# Bridge.net
KiCad netlist of a schematic drawn in Altium Designer
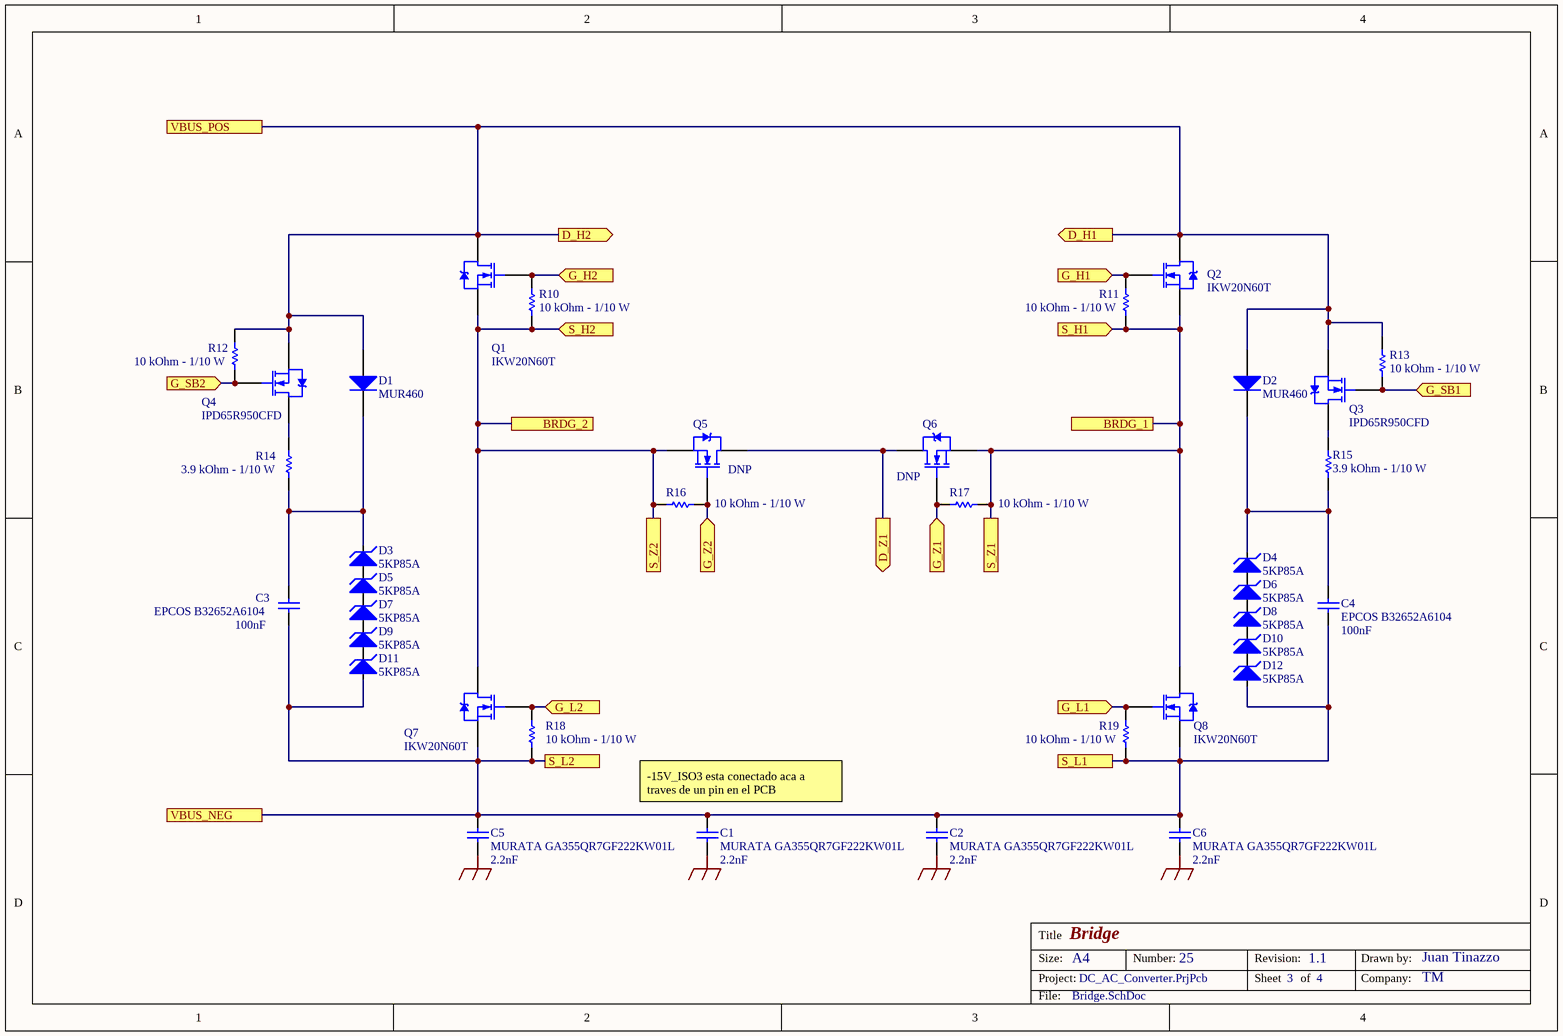
[diagram p0: Bridge.SchDoc]

(export (version "E")
  (design (tool "Eeschema 10.0.6"))
  (components
    (comp (ref "C1")
      (value "MURATA GA355QR7GF222KW01L")
      (footprint "Chip2PinSM127P600-8N_safety")
      (description "Safety Standard Certified Ceramic Y2 2.2nF 250Vac")
      (fields (field (name "ALTIUM_VALUE") "2.2nF") (field (name "PUBLISHER") "Altium Limited"))
      (libsource (lib "Capacitor") (part "MURATA GA355QR7GF222KW01L"))
    )
    (comp (ref "C2")
      (value "MURATA GA355QR7GF222KW01L")
      (footprint "Chip2PinSM127P600-8N_safety")
      (description "Safety Standard Certified Ceramic Y2 2.2nF 250Vac")
      (fields (field (name "ALTIUM_VALUE") "2.2nF") (field (name "PUBLISHER") "Altium Limited"))
      (libsource (lib "Capacitor") (part "MURATA GA355QR7GF222KW01L"))
    )
    (comp (ref "C3")
      (value "EPCOS B32652A6104")
      (footprint "MKP  pitch:15mm size:7mm x 18mm")
      (description "MKP High pulse (wound) 100nF 630Vdc")
      (fields (field (name "ALTIUM_VALUE") "100nF") (field (name "PUBLISHER") "Altium Limited"))
      (libsource (lib "Capacitor") (part "EPCOS B32652A6104"))
    )
    (comp (ref "C4")
      (value "EPCOS B32652A6104")
      (footprint "MKP  pitch:15mm size:7mm x 18mm")
      (description "MKP High pulse (wound) 100nF 630Vdc")
      (fields (field (name "ALTIUM_VALUE") "100nF") (field (name "PUBLISHER") "Altium Limited"))
      (libsource (lib "Capacitor") (part "EPCOS B32652A6104"))
    )
    (comp (ref "C5")
      (value "MURATA GA355QR7GF222KW01L")
      (footprint "Chip2PinSM127P600-8N_safety")
      (description "Safety Standard Certified Ceramic Y2 2.2nF 250Vac")
      (fields (field (name "ALTIUM_VALUE") "2.2nF") (field (name "PUBLISHER") "Altium Limited"))
      (libsource (lib "Capacitor") (part "MURATA GA355QR7GF222KW01L"))
    )
    (comp (ref "C6")
      (value "MURATA GA355QR7GF222KW01L")
      (footprint "Chip2PinSM127P600-8N_safety")
      (description "Safety Standard Certified Ceramic Y2 2.2nF 250Vac")
      (fields (field (name "ALTIUM_VALUE") "2.2nF") (field (name "PUBLISHER") "Altium Limited"))
      (libsource (lib "Capacitor") (part "MURATA GA355QR7GF222KW01L"))
    )
    (comp (ref "D1")
      (value "MUR460")
      (footprint "SMC")
      (description "Default Diode")
      (fields (field (name "PUBLISHER") "Altium Limited"))
      (libsource (lib "Miscellaneous Devices") (part "Diode"))
    )
    (comp (ref "D2")
      (value "MUR460")
      (footprint "SMC")
      (description "Default Diode")
      (fields (field (name "PUBLISHER") "Altium Limited"))
      (libsource (lib "Miscellaneous Devices") (part "Diode"))
    )
    (comp (ref "D3")
      (value "5KP85A")
      (footprint "DIODE-0.7")
      (description "Zener Diode")
      (fields (field (name "PUBLISHER") "Altium Limited"))
      (libsource (lib "Miscellaneous Devices") (part "D Zener"))
    )
    (comp (ref "D4")
      (value "5KP85A")
      (footprint "DIODE-0.7")
      (description "Zener Diode")
      (fields (field (name "PUBLISHER") "Altium Limited"))
      (libsource (lib "Miscellaneous Devices") (part "D Zener"))
    )
    (comp (ref "D5")
      (value "5KP85A")
      (footprint "DIODE-0.7")
      (description "Zener Diode")
      (fields (field (name "PUBLISHER") "Altium Limited"))
      (libsource (lib "Miscellaneous Devices") (part "D Zener"))
    )
    (comp (ref "D6")
      (value "5KP85A")
      (footprint "DIODE-0.7")
      (description "Zener Diode")
      (fields (field (name "PUBLISHER") "Altium Limited"))
      (libsource (lib "Miscellaneous Devices") (part "D Zener"))
    )
    (comp (ref "D7")
      (value "5KP85A")
      (footprint "DIODE-0.7")
      (description "Zener Diode")
      (fields (field (name "PUBLISHER") "Altium Limited"))
      (libsource (lib "Miscellaneous Devices") (part "D Zener"))
    )
    (comp (ref "D8")
      (value "5KP85A")
      (footprint "DIODE-0.7")
      (description "Zener Diode")
      (fields (field (name "PUBLISHER") "Altium Limited"))
      (libsource (lib "Miscellaneous Devices") (part "D Zener"))
    )
    (comp (ref "D9")
      (value "5KP85A")
      (footprint "DIODE-0.7")
      (description "Zener Diode")
      (fields (field (name "PUBLISHER") "Altium Limited"))
      (libsource (lib "Miscellaneous Devices") (part "D Zener"))
    )
    (comp (ref "D10")
      (value "5KP85A")
      (footprint "DIODE-0.7")
      (description "Zener Diode")
      (fields (field (name "PUBLISHER") "Altium Limited"))
      (libsource (lib "Miscellaneous Devices") (part "D Zener"))
    )
    (comp (ref "D11")
      (value "5KP85A")
      (footprint "DIODE-0.7")
      (description "Zener Diode")
      (fields (field (name "PUBLISHER") "Altium Limited"))
      (libsource (lib "Miscellaneous Devices") (part "D Zener"))
    )
    (comp (ref "D12")
      (value "5KP85A")
      (footprint "DIODE-0.7")
      (description "Zener Diode")
      (fields (field (name "PUBLISHER") "Altium Limited"))
      (libsource (lib "Miscellaneous Devices") (part "D Zener"))
    )
    (comp (ref "Q1")
      (value "IKW20N60T")
      (footprint "TO-247 Horiz. Heatsink")
      (description "IGBTs LOW LOSS DuoPack 600V 20A")
      (fields (field (name "PUBLISHER") "Altium Limited"))
      (libsource (lib "MOSFET") (part "IPx65R110CFD"))
    )
    (comp (ref "Q2")
      (value "IKW20N60T")
      (footprint "TO-247 Horiz. Heatsink")
      (description "IGBTs LOW LOSS DuoPack 600V 20A")
      (fields (field (name "PUBLISHER") "Altium Limited"))
      (libsource (lib "MOSFET") (part "IPx65R110CFD"))
    )
    (comp (ref "Q3")
      (value "IPD65R950CFD")
      (footprint "DPAK229P994X241-3N")
      (description "MOSFET N-Ch 700V 3.9A DPAK-2")
      (fields (field (name "PUBLISHER") "Altium Limited"))
      (libsource (lib "MOSFET") (part "IPD65R950CFD"))
    )
    (comp (ref "Q4")
      (value "IPD65R950CFD")
      (footprint "DPAK229P994X241-3N")
      (description "MOSFET N-Ch 700V 3.9A DPAK-2")
      (fields (field (name "PUBLISHER") "Altium Limited"))
      (libsource (lib "MOSFET") (part "IPD65R950CFD"))
    )
    (comp (ref "Q5")
      (value "DNP")
      (footprint "TO-247 Horiz. Heatsink")
      (description "IGBTs LOW LOSS DuoPack 600V 20A")
      (fields (field (name "PUBLISHER") "Altium Limited"))
      (libsource (lib "MOSFET") (part "IPx65R110CFD"))
    )
    (comp (ref "Q6")
      (value "DNP")
      (footprint "TO-247 Horiz. Heatsink")
      (description "IGBTs LOW LOSS DuoPack 600V 20A")
      (fields (field (name "PUBLISHER") "Altium Limited"))
      (libsource (lib "MOSFET") (part "IPx65R110CFD"))
    )
    (comp (ref "Q7")
      (value "IKW20N60T")
      (footprint "TO-247 Horiz. Heatsink")
      (description "IGBTs LOW LOSS DuoPack 600V 20A")
      (fields (field (name "PUBLISHER") "Altium Limited"))
      (libsource (lib "MOSFET") (part "IPx65R110CFD"))
    )
    (comp (ref "Q8")
      (value "IKW20N60T")
      (footprint "TO-247 Horiz. Heatsink")
      (description "IGBTs LOW LOSS DuoPack 600V 20A")
      (fields (field (name "PUBLISHER") "Altium Limited"))
      (libsource (lib "MOSFET") (part "IPx65R110CFD"))
    )
    (comp (ref "R10")
      (value "10 kOhm - 1/10 W")
      (footprint "RESC1608X50N")
      (description "Resistor")
      (fields
        (field (name "MANUFACTURER_PART_NUMBER") "CRCW060310K0FKEA")
        (field (name "MOUSER PART NUMBER") "71-CRCW0603-10K-E3")
      )
      (libsource (lib "SamacSys") (part "CRCW060310K0FKEA"))
    )
    (comp (ref "R11")
      (value "10 kOhm - 1/10 W")
      (footprint "RESC1608X50N")
      (description "Resistor")
      (fields
        (field (name "MANUFACTURER_PART_NUMBER") "CRCW060310K0FKEA")
        (field (name "MOUSER PART NUMBER") "71-CRCW0603-10K-E3")
      )
      (libsource (lib "SamacSys") (part "CRCW060310K0FKEA"))
    )
    (comp (ref "R12")
      (value "10 kOhm - 1/10 W")
      (footprint "RESC1608X50N")
      (description "Resistor")
      (fields
        (field (name "MANUFACTURER_PART_NUMBER") "CRCW060310K0FKEA")
        (field (name "MOUSER PART NUMBER") "71-CRCW0603-10K-E3")
      )
      (libsource (lib "SamacSys") (part "CRCW060310K0FKEA"))
    )
    (comp (ref "R13")
      (value "10 kOhm - 1/10 W")
      (footprint "RESC1608X50N")
      (description "Resistor")
      (fields
        (field (name "MANUFACTURER_PART_NUMBER") "CRCW060310K0FKEA")
        (field (name "MOUSER PART NUMBER") "71-CRCW0603-10K-E3")
      )
      (libsource (lib "SamacSys") (part "CRCW060310K0FKEA"))
    )
    (comp (ref "R14")
      (value "3.9 kOhm - 1/10 W")
      (footprint "RESC1608X50N")
      (description "Resistor")
      (fields
        (field (name "MANUFACTURER_PART_NUMBER") "CRCW06033K90FKEA")
        (field (name "MOUSER PART NUMBER") "71-CRCW0603-10K-E3")
      )
      (libsource (lib "SamacSys") (part "CRCW060310K0FKEA"))
    )
    (comp (ref "R15")
      (value "3.9 kOhm - 1/10 W")
      (footprint "RESC1608X50N")
      (description "Resistor")
      (fields
        (field (name "MANUFACTURER_PART_NUMBER") "CRCW06033K90FKEA")
        (field (name "MOUSER PART NUMBER") "71-CRCW0603-10K-E3")
      )
      (libsource (lib "SamacSys") (part "CRCW060310K0FKEA"))
    )
    (comp (ref "R16")
      (value "10 kOhm - 1/10 W")
      (footprint "RESC1608X50N")
      (description "Resistor")
      (fields
        (field (name "MANUFACTURER_PART_NUMBER") "CRCW060310K0FKEA")
        (field (name "MOUSER PART NUMBER") "71-CRCW0603-10K-E3")
      )
      (libsource (lib "SamacSys") (part "CRCW060310K0FKEA"))
    )
    (comp (ref "R17")
      (value "10 kOhm - 1/10 W")
      (footprint "RESC1608X50N")
      (description "Resistor")
      (fields
        (field (name "MANUFACTURER_PART_NUMBER") "CRCW060310K0FKEA")
        (field (name "MOUSER PART NUMBER") "71-CRCW0603-10K-E3")
      )
      (libsource (lib "SamacSys") (part "CRCW060310K0FKEA"))
    )
    (comp (ref "R18")
      (value "10 kOhm - 1/10 W")
      (footprint "RESC1608X50N")
      (description "Resistor")
      (fields
        (field (name "MANUFACTURER_PART_NUMBER") "CRCW060310K0FKEA")
        (field (name "MOUSER PART NUMBER") "71-CRCW0603-10K-E3")
      )
      (libsource (lib "SamacSys") (part "CRCW060310K0FKEA"))
    )
    (comp (ref "R19")
      (value "10 kOhm - 1/10 W")
      (footprint "RESC1608X50N")
      (description "Resistor")
      (fields
        (field (name "MANUFACTURER_PART_NUMBER") "CRCW060310K0FKEA")
        (field (name "MOUSER PART NUMBER") "71-CRCW0603-10K-E3")
      )
      (libsource (lib "SamacSys") (part "CRCW060310K0FKEA"))
    )
  )
  (nets
    (net (code "1") (name "/BRDG_1") (class "Default")
      (node (ref "Q2") (pin "3") (pinfunction "S_3") (pintype "passive"))
      (node (ref "Q6") (pin "3") (pinfunction "S_3") (pintype "passive"))
      (node (ref "Q8") (pin "2") (pinfunction "D_2") (pintype "passive"))
      (node (ref "R11") (pin "1") (pinfunction "1_1") (pintype "passive"))
      (node (ref "R17") (pin "1") (pinfunction "1_1") (pintype "passive"))
    )
    (net (code "2") (name "/BRDG_2") (class "Default")
      (node (ref "Q1") (pin "3") (pinfunction "S_3") (pintype "passive"))
      (node (ref "Q5") (pin "3") (pinfunction "S_3") (pintype "passive"))
      (node (ref "Q7") (pin "2") (pinfunction "D_2") (pintype "passive"))
      (node (ref "R10") (pin "1") (pinfunction "1_1") (pintype "passive"))
      (node (ref "R16") (pin "2") (pinfunction "2_2") (pintype "passive"))
    )
    (net (code "3") (name "/D_H1") (class "Default")
      (node (ref "D1") (pin "1") (pinfunction "A_1") (pintype "passive"))
      (node (ref "D2") (pin "1") (pinfunction "A_1") (pintype "passive"))
      (node (ref "Q1") (pin "2") (pinfunction "D_2") (pintype "passive"))
      (node (ref "Q2") (pin "2") (pinfunction "D_2") (pintype "passive"))
      (node (ref "Q3") (pin "3") (pinfunction "S_3") (pintype "passive"))
      (node (ref "Q4") (pin "3") (pinfunction "S_3") (pintype "passive"))
      (node (ref "R12") (pin "1") (pinfunction "1_1") (pintype "passive"))
      (node (ref "R13") (pin "2") (pinfunction "2_2") (pintype "passive"))
    )
    (net (code "4") (name "/D_Z1") (class "Default")
      (node (ref "Q5") (pin "2") (pinfunction "D_2") (pintype "passive"))
      (node (ref "Q6") (pin "2") (pinfunction "D_2") (pintype "passive"))
    )
    (net (code "5") (name "/G_H1") (class "Default")
      (node (ref "Q2") (pin "1") (pinfunction "G_1") (pintype "passive"))
      (node (ref "R11") (pin "2") (pinfunction "2_2") (pintype "passive"))
    )
    (net (code "6") (name "/G_H2") (class "Default")
      (node (ref "Q1") (pin "1") (pinfunction "G_1") (pintype "passive"))
      (node (ref "R10") (pin "2") (pinfunction "2_2") (pintype "passive"))
    )
    (net (code "7") (name "/G_L1") (class "Default")
      (node (ref "Q8") (pin "1") (pinfunction "G_1") (pintype "passive"))
      (node (ref "R19") (pin "2") (pinfunction "2_2") (pintype "passive"))
    )
    (net (code "8") (name "/G_L2") (class "Default")
      (node (ref "Q7") (pin "1") (pinfunction "G_1") (pintype "passive"))
      (node (ref "R18") (pin "2") (pinfunction "2_2") (pintype "passive"))
    )
    (net (code "9") (name "/G_SB1") (class "Default")
      (node (ref "Q3") (pin "1") (pinfunction "G_1") (pintype "passive"))
      (node (ref "R13") (pin "1") (pinfunction "1_1") (pintype "passive"))
    )
    (net (code "10") (name "/G_SB2") (class "Default")
      (node (ref "Q4") (pin "1") (pinfunction "G_1") (pintype "passive"))
      (node (ref "R12") (pin "2") (pinfunction "2_2") (pintype "passive"))
    )
    (net (code "11") (name "/G_Z1") (class "Default")
      (node (ref "Q6") (pin "1") (pinfunction "G_1") (pintype "passive"))
      (node (ref "R17") (pin "2") (pinfunction "2_2") (pintype "passive"))
    )
    (net (code "12") (name "/G_Z2") (class "Default")
      (node (ref "Q5") (pin "1") (pinfunction "G_1") (pintype "passive"))
      (node (ref "R16") (pin "1") (pinfunction "1_1") (pintype "passive"))
    )
    (net (code "13") (name "/S_L1") (class "Default")
      (node (ref "C1") (pin "2") (pinfunction "2_2") (pintype "passive"))
      (node (ref "C2") (pin "2") (pinfunction "2_2") (pintype "passive"))
      (node (ref "C3") (pin "1") (pinfunction "1_1") (pintype "passive"))
      (node (ref "C4") (pin "1") (pinfunction "1_1") (pintype "passive"))
      (node (ref "C5") (pin "2") (pinfunction "2_2") (pintype "passive"))
      (node (ref "C6") (pin "2") (pinfunction "2_2") (pintype "passive"))
      (node (ref "D11") (pin "1") (pinfunction "A_1") (pintype "passive"))
      (node (ref "D12") (pin "1") (pinfunction "A_1") (pintype "passive"))
      (node (ref "Q7") (pin "3") (pinfunction "S_3") (pintype "passive"))
      (node (ref "Q8") (pin "3") (pinfunction "S_3") (pintype "passive"))
      (node (ref "R18") (pin "1") (pinfunction "1_1") (pintype "passive"))
      (node (ref "R19") (pin "1") (pinfunction "1_1") (pintype "passive"))
    )
    (net (code "14") (name "EARTH") (class "Default")
      (node (ref "C1") (pin "1") (pinfunction "1_1") (pintype "passive"))
      (node (ref "C2") (pin "1") (pinfunction "1_1") (pintype "passive"))
      (node (ref "C5") (pin "1") (pinfunction "1_1") (pintype "passive"))
      (node (ref "C6") (pin "1") (pinfunction "1_1") (pintype "passive"))
    )
    (net (code "15") (name "Net-(D1-K)") (class "Default")
      (node (ref "C3") (pin "2") (pinfunction "2_2") (pintype "passive"))
      (node (ref "D1") (pin "2") (pinfunction "K_2") (pintype "passive"))
      (node (ref "D3") (pin "2") (pinfunction "K_2") (pintype "passive"))
      (node (ref "R14") (pin "2") (pinfunction "2_2") (pintype "passive"))
    )
    (net (code "16") (name "Net-(D2-K)") (class "Default")
      (node (ref "C4") (pin "2") (pinfunction "2_2") (pintype "passive"))
      (node (ref "D2") (pin "2") (pinfunction "K_2") (pintype "passive"))
      (node (ref "D4") (pin "2") (pinfunction "K_2") (pintype "passive"))
      (node (ref "R15") (pin "2") (pinfunction "2_2") (pintype "passive"))
    )
    (net (code "17") (name "Net-(D3-A)") (class "Default")
      (node (ref "D3") (pin "1") (pinfunction "A_1") (pintype "passive"))
      (node (ref "D5") (pin "2") (pinfunction "K_2") (pintype "passive"))
    )
    (net (code "18") (name "Net-(D4-A)") (class "Default")
      (node (ref "D4") (pin "1") (pinfunction "A_1") (pintype "passive"))
      (node (ref "D6") (pin "2") (pinfunction "K_2") (pintype "passive"))
    )
    (net (code "19") (name "Net-(D5-A)") (class "Default")
      (node (ref "D5") (pin "1") (pinfunction "A_1") (pintype "passive"))
      (node (ref "D7") (pin "2") (pinfunction "K_2") (pintype "passive"))
    )
    (net (code "20") (name "Net-(D6-A)") (class "Default")
      (node (ref "D6") (pin "1") (pinfunction "A_1") (pintype "passive"))
      (node (ref "D8") (pin "2") (pinfunction "K_2") (pintype "passive"))
    )
    (net (code "21") (name "Net-(D7-A)") (class "Default")
      (node (ref "D7") (pin "1") (pinfunction "A_1") (pintype "passive"))
      (node (ref "D9") (pin "2") (pinfunction "K_2") (pintype "passive"))
    )
    (net (code "22") (name "Net-(D10-A)") (class "Default")
      (node (ref "D10") (pin "1") (pinfunction "A_1") (pintype "passive"))
      (node (ref "D12") (pin "2") (pinfunction "K_2") (pintype "passive"))
    )
    (net (code "23") (name "Net-(D10-K)") (class "Default")
      (node (ref "D10") (pin "2") (pinfunction "K_2") (pintype "passive"))
      (node (ref "D8") (pin "1") (pinfunction "A_1") (pintype "passive"))
    )
    (net (code "24") (name "Net-(D11-K)") (class "Default")
      (node (ref "D11") (pin "2") (pinfunction "K_2") (pintype "passive"))
      (node (ref "D9") (pin "1") (pinfunction "A_1") (pintype "passive"))
    )
    (net (code "25") (name "Net-(Q3-D)") (class "Default")
      (node (ref "Q3") (pin "2") (pinfunction "D_2") (pintype "passive"))
      (node (ref "R15") (pin "1") (pinfunction "1_1") (pintype "passive"))
    )
    (net (code "26") (name "Net-(Q4-D)") (class "Default")
      (node (ref "Q4") (pin "2") (pinfunction "D_2") (pintype "passive"))
      (node (ref "R14") (pin "1") (pinfunction "1_1") (pintype "passive"))
    )
  )
)
